# DSO_IO.net
KiCad netlist of a schematic drawn in Altium Designer
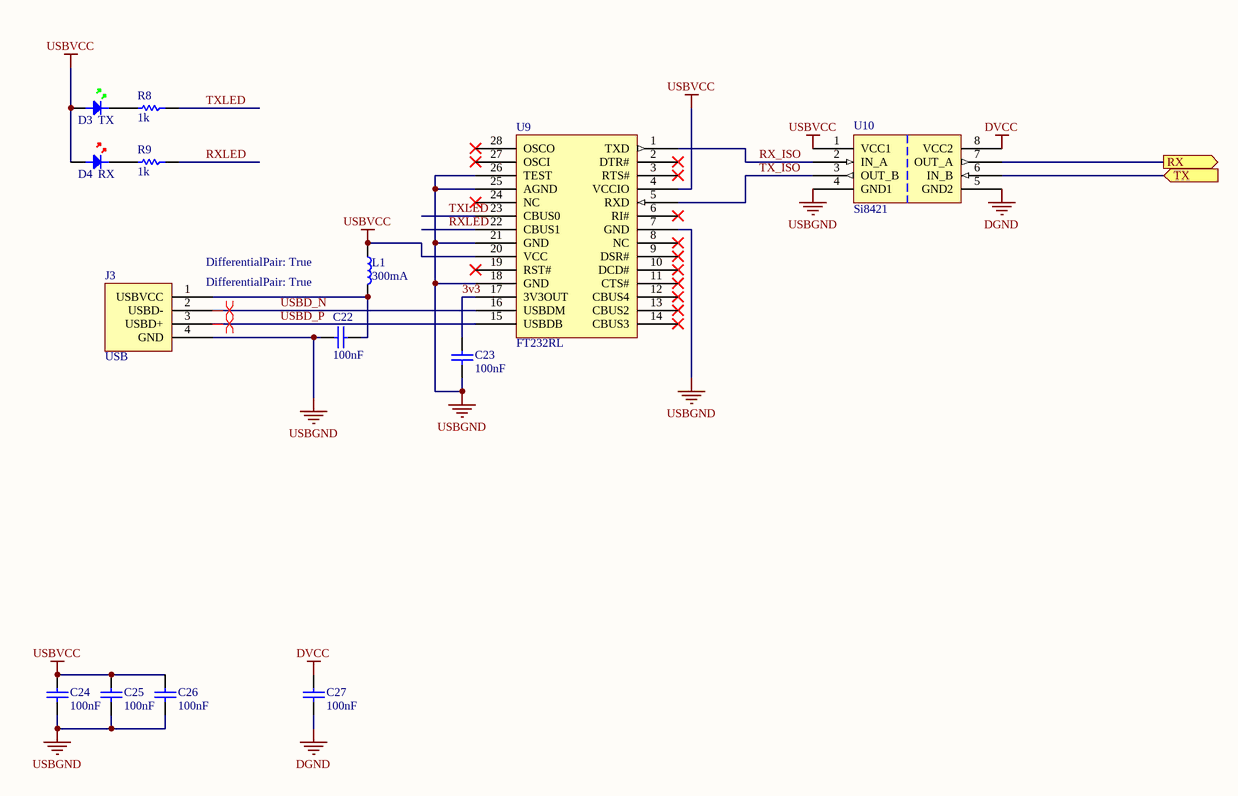
[diagram p0: DSO_IO.SchDoc]

(export (version "E")
  (design (tool "Eeschema 10.0.6"))
  (components
    (comp (ref "C22")
      (value "100nF")
      (footprint "0805C")
      (description "Capacitor")
      (fields (field (name "REVIEWED BY") "RM - 2018/08/05"))
      (libsource (lib "DSO") (part "C"))
    )
    (comp (ref "C23")
      (value "100nF")
      (footprint "0805C")
      (description "Capacitor")
      (fields (field (name "REVIEWED BY") "RM - 2018/08/05"))
      (libsource (lib "DSO") (part "C"))
    )
    (comp (ref "C24")
      (value "100nF")
      (footprint "0805C")
      (description "Capacitor")
      (fields (field (name "REVIEWED BY") "RM - 2018/08/05"))
      (libsource (lib "DSO") (part "C"))
    )
    (comp (ref "C25")
      (value "100nF")
      (footprint "0805C")
      (description "Capacitor")
      (fields (field (name "REVIEWED BY") "RM - 2018/08/05"))
      (libsource (lib "DSO") (part "C"))
    )
    (comp (ref "C26")
      (value "100nF")
      (footprint "0805C")
      (description "Capacitor")
      (fields (field (name "REVIEWED BY") "RM - 2018/08/05"))
      (libsource (lib "DSO") (part "C"))
    )
    (comp (ref "C27")
      (value "100nF")
      (footprint "0805C")
      (description "Capacitor")
      (fields (field (name "REVIEWED BY") "RM - 2018/08/05"))
      (libsource (lib "DSO") (part "C"))
    )
    (comp (ref "D3")
      (value "TX")
      (footprint "0805D-GREEN")
      (description "Light Emitting Diode")
      (fields (field (name "REVIEWED BY") "RM - 2018/08/05"))
      (libsource (lib "DSO") (part "LED GREEN"))
    )
    (comp (ref "D4")
      (value "RX")
      (footprint "0805D-RED")
      (description "Light Emitting Diode")
      (fields (field (name "REVIEWED BY") "RM - 2018/08/05"))
      (libsource (lib "DSO") (part "LED RED"))
    )
    (comp (ref "J3")
      (value "USB")
      (footprint "USBPLUG")
      (description "USB B Type Connector")
      (fields (field (name "REVIEWED BY") "RM - 2018/08/05"))
      (libsource (lib "DSO") (part "USBPLUG"))
    )
    (comp (ref "L1")
      (value "300mA")
      (footprint "0805")
      (description "Inductor")
      (fields (field (name "REVIEWED BY") "RM - 2018/08/05"))
      (libsource (lib "DSO") (part "I"))
    )
    (comp (ref "R8")
      (value "1k")
      (footprint "0805")
      (description "Resistor")
      (fields (field (name "REVIEWED BY") "RM - 2018/08/05"))
      (libsource (lib "DSO") (part "R"))
    )
    (comp (ref "R9")
      (value "1k")
      (footprint "0805")
      (description "Resistor")
      (fields (field (name "REVIEWED BY") "RM - 2018/08/05"))
      (libsource (lib "DSO") (part "R"))
    )
    (comp (ref "U9")
      (value "FT232RL")
      (footprint "SSOP-28")
      (description "USB to Serial bridge")
      (fields (field (name "REVIEWED BY") "RM - 2018/08/05"))
      (libsource (lib "DSO") (part "FT232RL"))
    )
    (comp (ref "U10")
      (value "Si8421")
      (footprint "SOIC-8")
      (description "Dual Channel Digital Isolator Both Ways")
      (fields (field (name "REVIEWED BY") "RM - 2018/08/05"))
      (libsource (lib "DSO") (part "Si8421"))
    )
  )
  (nets
    (net (code "1") (name "/3v3") (class "Default")
      (node (ref "C23") (pin "1") (pinfunction "1_1") (pintype "passive"))
      (node (ref "U9") (pin "17") (pinfunction "3V3OUT_17") (pintype "passive"))
    )
    (net (code "2") (name "/RX") (class "Default")
      (node (ref "U10") (pin "7") (pinfunction "OUT_A_7") (pintype "output"))
    )
    (net (code "3") (name "/RXLED") (class "Default")
      (node (ref "R9") (pin "1") (pintype "passive"))
      (node (ref "U9") (pin "22") (pinfunction "CBUS1_22") (pintype "passive"))
    )
    (net (code "4") (name "/RX_ISO") (class "Default")
      (node (ref "U10") (pin "2") (pinfunction "IN_A_2") (pintype "input"))
      (node (ref "U9") (pin "1") (pinfunction "TXD_1") (pintype "output"))
    )
    (net (code "5") (name "/TX") (class "Default")
      (node (ref "U10") (pin "6") (pinfunction "IN_B_6") (pintype "input"))
    )
    (net (code "6") (name "/TXLED") (class "Default")
      (node (ref "R8") (pin "1") (pintype "passive"))
      (node (ref "U9") (pin "23") (pinfunction "CBUS0_23") (pintype "passive"))
    )
    (net (code "7") (name "/TX_ISO") (class "Default")
      (node (ref "U10") (pin "3") (pinfunction "OUT_B_3") (pintype "output"))
      (node (ref "U9") (pin "5") (pinfunction "RXD_5") (pintype "input"))
    )
    (net (code "8") (name "/USBD_N") (class "Default")
      (node (ref "J3") (pin "2") (pinfunction "USBD-_2") (pintype "passive"))
      (node (ref "U9") (pin "16") (pinfunction "USBDM_16") (pintype "passive"))
    )
    (net (code "9") (name "/USBD_P") (class "Default")
      (node (ref "J3") (pin "3") (pinfunction "USBD+_3") (pintype "passive"))
      (node (ref "U9") (pin "15") (pinfunction "USBDB_15") (pintype "passive"))
    )
    (net (code "10") (name "DGND") (class "Default")
      (node (ref "C27") (pin "2") (pinfunction "2_2") (pintype "passive"))
      (node (ref "U10") (pin "5") (pinfunction "GND2_5") (pintype "passive"))
    )
    (net (code "11") (name "DVCC") (class "Default")
      (node (ref "C27") (pin "1") (pinfunction "1_1") (pintype "passive"))
      (node (ref "U10") (pin "8") (pinfunction "VCC2_8") (pintype "passive"))
    )
    (net (code "12") (name "Net-(D3-PadK)") (class "Default")
      (node (ref "D3") (pin "K") (pinfunction "K_K") (pintype "passive"))
      (node (ref "R8") (pin "2") (pintype "passive"))
    )
    (net (code "13") (name "Net-(D4-PadK)") (class "Default")
      (node (ref "D4") (pin "K") (pinfunction "K_K") (pintype "passive"))
      (node (ref "R9") (pin "2") (pintype "passive"))
    )
    (net (code "14") (name "Net-(J3-USBVCC)") (class "Default")
      (node (ref "C22") (pin "1") (pinfunction "1_1") (pintype "passive"))
      (node (ref "J3") (pin "1") (pinfunction "USBVCC_1") (pintype "passive"))
      (node (ref "L1") (pin "2") (pinfunction "2_2") (pintype "passive"))
    )
    (net (code "15") (name "USBGND") (class "Default")
      (node (ref "C22") (pin "2") (pinfunction "2_2") (pintype "passive"))
      (node (ref "C23") (pin "2") (pinfunction "2_2") (pintype "passive"))
      (node (ref "C24") (pin "2") (pinfunction "2_2") (pintype "passive"))
      (node (ref "C25") (pin "2") (pinfunction "2_2") (pintype "passive"))
      (node (ref "C26") (pin "2") (pinfunction "2_2") (pintype "passive"))
      (node (ref "J3") (pin "4") (pinfunction "GND_4") (pintype "passive"))
      (node (ref "U10") (pin "4") (pinfunction "GND1_4") (pintype "passive"))
      (node (ref "U9") (pin "18") (pinfunction "GND_18") (pintype "passive"))
      (node (ref "U9") (pin "21") (pinfunction "GND_21") (pintype "passive"))
      (node (ref "U9") (pin "25") (pinfunction "AGND_25") (pintype "passive"))
      (node (ref "U9") (pin "26") (pinfunction "TEST_26") (pintype "passive"))
      (node (ref "U9") (pin "7") (pinfunction "GND_7") (pintype "passive"))
    )
    (net (code "16") (name "USBVCC") (class "Default")
      (node (ref "C24") (pin "1") (pinfunction "1_1") (pintype "passive"))
      (node (ref "C25") (pin "1") (pinfunction "1_1") (pintype "passive"))
      (node (ref "C26") (pin "1") (pinfunction "1_1") (pintype "passive"))
      (node (ref "D3") (pin "A") (pinfunction "A_A") (pintype "passive"))
      (node (ref "D4") (pin "A") (pinfunction "A_A") (pintype "passive"))
      (node (ref "L1") (pin "1") (pinfunction "1_1") (pintype "passive"))
      (node (ref "U10") (pin "1") (pinfunction "VCC1_1") (pintype "passive"))
      (node (ref "U9") (pin "20") (pinfunction "VCC_20") (pintype "passive"))
      (node (ref "U9") (pin "4") (pinfunction "VCCIO_4") (pintype "passive"))
    )
    (net (code "17") (name "unconnected-(U9-CBUS2-Pad13)") (class "Default")
      (node (ref "U9") (pin "13") (pinfunction "CBUS2_13") (pintype "passive+no_connect"))
    )
    (net (code "18") (name "unconnected-(U9-CBUS3-Pad14)") (class "Default")
      (node (ref "U9") (pin "14") (pinfunction "CBUS3_14") (pintype "passive+no_connect"))
    )
    (net (code "19") (name "unconnected-(U9-CBUS4-Pad12)") (class "Default")
      (node (ref "U9") (pin "12") (pinfunction "CBUS4_12") (pintype "passive+no_connect"))
    )
    (net (code "20") (name "unconnected-(U9-CTS#-Pad11)") (class "Default")
      (node (ref "U9") (pin "11") (pinfunction "CTS#_11") (pintype "passive+no_connect"))
    )
    (net (code "21") (name "unconnected-(U9-DCD#-Pad10)") (class "Default")
      (node (ref "U9") (pin "10") (pinfunction "DCD#_10") (pintype "passive+no_connect"))
    )
    (net (code "22") (name "unconnected-(U9-DSR#-Pad9)") (class "Default")
      (node (ref "U9") (pin "9") (pinfunction "DSR#_9") (pintype "passive+no_connect"))
    )
    (net (code "23") (name "unconnected-(U9-DTR#-Pad2)") (class "Default")
      (node (ref "U9") (pin "2") (pinfunction "DTR#_2") (pintype "passive+no_connect"))
    )
    (net (code "24") (name "unconnected-(U9-NC-Pad8)") (class "Default")
      (node (ref "U9") (pin "8") (pinfunction "NC_8") (pintype "passive+no_connect"))
    )
    (net (code "25") (name "unconnected-(U9-NC-Pad24)") (class "Default")
      (node (ref "U9") (pin "24") (pinfunction "NC_24") (pintype "passive+no_connect"))
    )
    (net (code "26") (name "unconnected-(U9-OSCI-Pad27)") (class "Default")
      (node (ref "U9") (pin "27") (pinfunction "OSCI_27") (pintype "passive+no_connect"))
    )
    (net (code "27") (name "unconnected-(U9-OSCO-Pad28)") (class "Default")
      (node (ref "U9") (pin "28") (pinfunction "OSCO_28") (pintype "passive+no_connect"))
    )
    (net (code "28") (name "unconnected-(U9-RI#-Pad6)") (class "Default")
      (node (ref "U9") (pin "6") (pinfunction "RI#_6") (pintype "passive+no_connect"))
    )
    (net (code "29") (name "unconnected-(U9-RST#-Pad19)") (class "Default")
      (node (ref "U9") (pin "19") (pinfunction "RST#_19") (pintype "passive+no_connect"))
    )
    (net (code "30") (name "unconnected-(U9-RTS#-Pad3)") (class "Default")
      (node (ref "U9") (pin "3") (pinfunction "RTS#_3") (pintype "passive+no_connect"))
    )
  )
)
